# BATT_INPUT_TEST_BED_V2.net
KiCad netlist of a schematic drawn in EAGLE
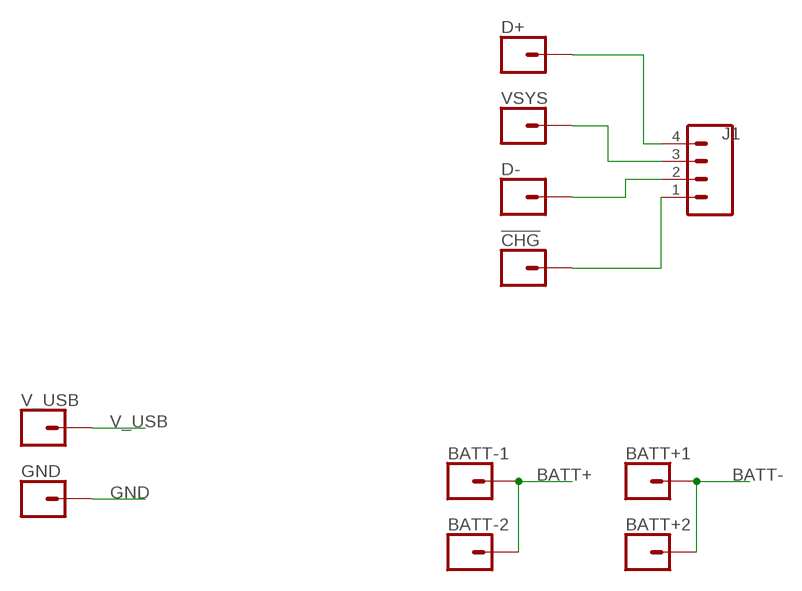
[diagram p0: schematic, sheet 1]

(export (version "E")
  (design (tool "Eeschema 10.0.6"))
  (components
    (comp (ref "!CHG!")
      (value "CONN_01POGOPIN_HOLE_LARGE")
      (footprint "eagle-import:1X01_POGOPIN_HOLE_0.061_DIA")
      (libsource (lib "eagle-import") (part "CONN_01POGOPIN_HOLE_LARGE"))
    )
    (comp (ref "BATT+1")
      (value "CONN_01POGOPIN_HOLE_LARGE")
      (footprint "eagle-import:1X01_POGOPIN_HOLE_0.061_DIA")
      (libsource (lib "eagle-import") (part "CONN_01POGOPIN_HOLE_LARGE"))
    )
    (comp (ref "BATT+2")
      (value "CONN_01POGOPIN_HOLE_LARGE")
      (footprint "eagle-import:1X01_POGOPIN_HOLE_0.061_DIA")
      (libsource (lib "eagle-import") (part "CONN_01POGOPIN_HOLE_LARGE"))
    )
    (comp (ref "BATT-1")
      (value "CONN_01POGOPIN_HOLE_LARGE")
      (footprint "eagle-import:1X01_POGOPIN_HOLE_0.061_DIA")
      (libsource (lib "eagle-import") (part "CONN_01POGOPIN_HOLE_LARGE"))
    )
    (comp (ref "BATT-2")
      (value "CONN_01POGOPIN_HOLE_LARGE")
      (footprint "eagle-import:1X01_POGOPIN_HOLE_0.061_DIA")
      (libsource (lib "eagle-import") (part "CONN_01POGOPIN_HOLE_LARGE"))
    )
    (comp (ref "D+")
      (value "CONN_01POGOPIN_HOLE_LARGE")
      (footprint "eagle-import:1X01_POGOPIN_HOLE_0.061_DIA")
      (libsource (lib "eagle-import") (part "CONN_01POGOPIN_HOLE_LARGE"))
    )
    (comp (ref "D-")
      (value "CONN_01POGOPIN_HOLE_LARGE")
      (footprint "eagle-import:1X01_POGOPIN_HOLE_0.061_DIA")
      (libsource (lib "eagle-import") (part "CONN_01POGOPIN_HOLE_LARGE"))
    )
    (comp (ref "GND")
      (value "CONN_01POGOPIN_HOLE_LARGE")
      (footprint "eagle-import:1X01_POGOPIN_HOLE_0.061_DIA")
      (libsource (lib "eagle-import") (part "CONN_01POGOPIN_HOLE_LARGE"))
    )
    (comp (ref "J1")
      (value "FEMALE 2x3")
      (footprint "eagle-import:1X04")
      (libsource (lib "eagle-import") (part "CONN_04"))
    )
    (comp (ref "VSYS")
      (value "CONN_01POGOPIN_HOLE_LARGE")
      (footprint "eagle-import:1X01_POGOPIN_HOLE_0.061_DIA")
      (libsource (lib "eagle-import") (part "CONN_01POGOPIN_HOLE_LARGE"))
    )
    (comp (ref "V_USB")
      (value "CONN_01POGOPIN_HOLE_LARGE")
      (footprint "eagle-import:1X01_POGOPIN_HOLE_0.061_DIA")
      (libsource (lib "eagle-import") (part "CONN_01POGOPIN_HOLE_LARGE"))
    )
  )
  (nets
    (net (code "1") (name "/BATT+") (class "Default")
      (node (ref "BATT-1") (pin "2") (pinfunction "1_2") (pintype "passive"))
      (node (ref "BATT-2") (pin "2") (pinfunction "1_2") (pintype "passive"))
    )
    (net (code "2") (name "/BATT-") (class "Default")
      (node (ref "BATT+1") (pin "2") (pinfunction "1_2") (pintype "passive"))
      (node (ref "BATT+2") (pin "2") (pinfunction "1_2") (pintype "passive"))
    )
    (net (code "3") (name "/GND") (class "Default")
      (node (ref "GND") (pin "2") (pinfunction "1_2") (pintype "passive"))
    )
    (net (code "4") (name "/V_USB") (class "Default")
      (node (ref "V_USB") (pin "2") (pinfunction "1_2") (pintype "passive"))
    )
    (net (code "5") (name "Net-(!CHG!-1)") (class "Default")
      (node (ref "!CHG!") (pin "2") (pinfunction "1_2") (pintype "passive"))
      (node (ref "J1") (pin "1") (pinfunction "1_1") (pintype "passive"))
    )
    (net (code "6") (name "Net-(D+-1)") (class "Default")
      (node (ref "D+") (pin "2") (pinfunction "1_2") (pintype "passive"))
      (node (ref "J1") (pin "4") (pinfunction "4_4") (pintype "passive"))
    )
    (net (code "7") (name "Net-(D--1)") (class "Default")
      (node (ref "D-") (pin "2") (pinfunction "1_2") (pintype "passive"))
      (node (ref "J1") (pin "2") (pinfunction "2_2") (pintype "passive"))
    )
    (net (code "8") (name "Net-(VSYS-1)") (class "Default")
      (node (ref "J1") (pin "3") (pinfunction "3_3") (pintype "passive"))
      (node (ref "VSYS") (pin "2") (pinfunction "1_2") (pintype "passive"))
    )
  )
)
